# design.net
KiCad netlist of a schematic drawn in EAGLE
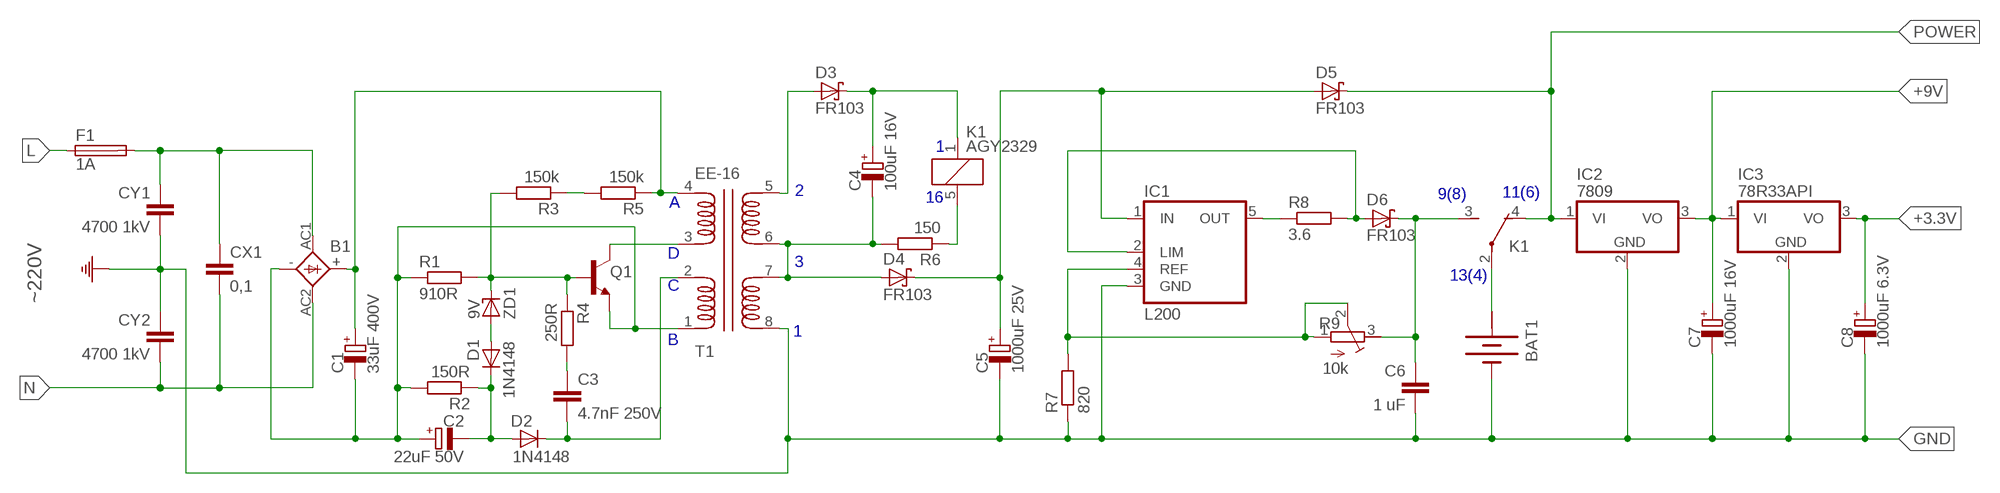
[diagram p0: schematic, sheet 1]

(export (version "E")
  (design (tool "Eeschema 10.0.6"))
  (components
    (comp (ref "B1")
      (value "1KAB")
      (footprint "eagle-import:1KAB")
      (libsource (lib "eagle-import") (part "1KAB"))
    )
    (comp (ref "BAT1")
      (value "BATTERY")
      (footprint "eagle-import:BATTERY")
      (libsource (lib "eagle-import") (part "BATTERY"))
    )
    (comp (ref "C1")
      (value "33uF 400V")
      (footprint "eagle-import:085CS_1AR")
      (libsource (lib "eagle-import") (part "CPOL-EU085CS-1AR"))
    )
    (comp (ref "C2")
      (value "22uF 50V")
      (footprint "eagle-import:085CS_1AR")
      (libsource (lib "eagle-import") (part "CPOL-EU085CS-1AR"))
    )
    (comp (ref "C3")
      (value "4.7nF 250V")
      (footprint "eagle-import:C025-024X044")
      (libsource (lib "eagle-import") (part "C-EU025-024X044"))
    )
    (comp (ref "C4")
      (value "100uF 16V")
      (footprint "eagle-import:085CS_1AR")
      (libsource (lib "eagle-import") (part "CPOL-EU085CS-1AR"))
    )
    (comp (ref "C5")
      (value "1000uF 25V")
      (footprint "eagle-import:085CS_1AR")
      (libsource (lib "eagle-import") (part "CPOL-EU085CS-1AR"))
    )
    (comp (ref "C6")
      (value "1 uF")
      (footprint "eagle-import:C025-024X044")
      (libsource (lib "eagle-import") (part "C-EU025-024X044"))
    )
    (comp (ref "C7")
      (value "1000uF 16V")
      (footprint "eagle-import:085CS_1AR")
      (libsource (lib "eagle-import") (part "CPOL-EU085CS-1AR"))
    )
    (comp (ref "C8")
      (value "1000uF 6.3V")
      (footprint "eagle-import:085CS_1AR")
      (libsource (lib "eagle-import") (part "CPOL-EU085CS-1AR"))
    )
    (comp (ref "CX1")
      (value "0,1")
      (footprint "eagle-import:C025-024X044")
      (libsource (lib "eagle-import") (part "C-EU025-024X044"))
    )
    (comp (ref "CY1")
      (value "4700 1kV")
      (footprint "eagle-import:C025-024X044")
      (libsource (lib "eagle-import") (part "C-EU025-024X044"))
    )
    (comp (ref "CY2")
      (value "4700 1kV")
      (footprint "eagle-import:C025-024X044")
      (libsource (lib "eagle-import") (part "C-EU025-024X044"))
    )
    (comp (ref "D1")
      (value "1N4148")
      (footprint "eagle-import:DO41-10")
      (libsource (lib "eagle-import") (part "1N4004"))
    )
    (comp (ref "D2")
      (value "1N4148")
      (footprint "eagle-import:DO41-10")
      (libsource (lib "eagle-import") (part "1N4004"))
    )
    (comp (ref "D3")
      (value "FR103")
      (footprint "eagle-import:SOT23")
      (libsource (lib "eagle-import") (part "BAS40"))
    )
    (comp (ref "D4")
      (value "FR103")
      (footprint "eagle-import:SOT23")
      (libsource (lib "eagle-import") (part "BAS40"))
    )
    (comp (ref "D5")
      (value "FR103")
      (footprint "eagle-import:SOT23")
      (libsource (lib "eagle-import") (part "BAS40"))
    )
    (comp (ref "D6")
      (value "FR103")
      (footprint "eagle-import:SOT23")
      (libsource (lib "eagle-import") (part "BAS40"))
    )
    (comp (ref "F1")
      (value "1А")
      (footprint "eagle-import:GSH15")
      (fields (field (name "MPN") "64900001039"))
      (libsource (lib "eagle-import") (part "GSH15"))
    )
    (comp (ref "IC1")
      (value "L200")
      (footprint "eagle-import:L200S")
      (libsource (lib "eagle-import") (part "L200"))
    )
    (comp (ref "IC2")
      (value "7809")
      (footprint "eagle-import:TO220H")
      (libsource (lib "eagle-import") (part "78T08"))
    )
    (comp (ref "IC3")
      (value "78R33API")
      (footprint "eagle-import:TO220H")
      (libsource (lib "eagle-import") (part "78T08"))
    )
    (comp (ref "K1")
      (value "AGY2329")
      (footprint "eagle-import:G5SB")
      (libsource (lib "eagle-import") (part "G5SB"))
    )
    (comp (ref "Q1")
      (value "2N706")
      (footprint "eagle-import:TO18")
      (libsource (lib "eagle-import") (part "2N706"))
    )
    (comp (ref "R1")
      (value "910R")
      (footprint "eagle-import:0204V")
      (libsource (lib "eagle-import") (part "R-EU_0204/2V"))
    )
    (comp (ref "R2")
      (value "150R")
      (footprint "eagle-import:0204V")
      (libsource (lib "eagle-import") (part "R-EU_0204/2V"))
    )
    (comp (ref "R3")
      (value "150k")
      (footprint "eagle-import:0204V")
      (libsource (lib "eagle-import") (part "R-EU_0204/2V"))
    )
    (comp (ref "R4")
      (value "250R")
      (footprint "eagle-import:0204V")
      (libsource (lib "eagle-import") (part "R-EU_0204/2V"))
    )
    (comp (ref "R5")
      (value "150k")
      (footprint "eagle-import:0204V")
      (libsource (lib "eagle-import") (part "R-EU_0204/2V"))
    )
    (comp (ref "R6")
      (value "150")
      (footprint "eagle-import:0204V")
      (libsource (lib "eagle-import") (part "R-EU_0204/2V"))
    )
    (comp (ref "R7")
      (value "820")
      (footprint "eagle-import:0204V")
      (libsource (lib "eagle-import") (part "R-EU_0204/2V"))
    )
    (comp (ref "R8")
      (value "3.6")
      (footprint "eagle-import:0204V")
      (libsource (lib "eagle-import") (part "R-EU_0204/2V"))
    )
    (comp (ref "R9")
      (value "10k")
      (footprint "eagle-import:RTRIM4G_J")
      (libsource (lib "eagle-import") (part "R-TRIMM4G/J"))
    )
    (comp (ref "T1")
      (value "EE-16")
      (footprint "eagle-import:HDS28G2")
      (libsource (lib "eagle-import") (part "HDS28G2"))
    )
    (comp (ref "ZD1")
      (value "9V")
      (footprint "eagle-import:C1702-15")
      (libsource (lib "eagle-import") (part "1N5333"))
    )
  )
  (nets
    (net (code "1") (name "+3.3V") (class "Default")
      (node (ref "C8") (pin "+") (pinfunction "+_+") (pintype "passive"))
      (node (ref "IC3") (pin "3") (pinfunction "VO_3") (pintype "passive"))
    )
    (net (code "2") (name "+9V") (class "Default")
      (node (ref "C7") (pin "+") (pinfunction "+_+") (pintype "passive"))
      (node (ref "IC2") (pin "3") (pinfunction "VO_3") (pintype "passive"))
      (node (ref "IC3") (pin "1") (pinfunction "VI_1") (pintype "input"))
    )
    (net (code "3") (name "/+") (class "Default")
      (node (ref "BAT1") (pin "+@1") (pinfunction "+_+@1") (pintype "power_in"))
    )
    (net (code "4") (name "GND") (class "Default")
      (node (ref "BAT1") (pin "-") (pinfunction "-_-") (pintype "power_in"))
      (node (ref "C5") (pin "-") (pinfunction "-_-") (pintype "passive"))
      (node (ref "C6") (pin "2") (pinfunction "2_2") (pintype "passive"))
      (node (ref "C7") (pin "-") (pinfunction "-_-") (pintype "passive"))
      (node (ref "C8") (pin "-") (pinfunction "-_-") (pintype "passive"))
      (node (ref "CY1") (pin "2") (pinfunction "2_2") (pintype "passive"))
      (node (ref "CY2") (pin "1") (pinfunction "1_1") (pintype "passive"))
      (node (ref "IC1") (pin "3") (pinfunction "GND_3") (pintype "passive"))
      (node (ref "IC2") (pin "2") (pinfunction "GND_2") (pintype "passive"))
      (node (ref "IC3") (pin "2") (pinfunction "GND_2") (pintype "passive"))
      (node (ref "R7") (pin "1") (pinfunction "1_1") (pintype "passive"))
      (node (ref "T1") (pin "8") (pinfunction "S1.1_8") (pintype "passive"))
    )
    (net (code "5") (name "L") (class "Default")
      (node (ref "F1") (pin "1") (pinfunction "1_1") (pintype "passive"))
    )
    (net (code "6") (name "N") (class "Default")
      (node (ref "B1") (pin "AC2") (pinfunction "AC2_AC2") (pintype "passive"))
      (node (ref "CX1") (pin "2") (pinfunction "2_2") (pintype "passive"))
      (node (ref "CY2") (pin "2") (pinfunction "2_2") (pintype "passive"))
    )
    (net (code "7") (name "Net-(B1-PadAC1)") (class "Default")
      (node (ref "B1") (pin "AC1") (pinfunction "AC1_AC1") (pintype "passive"))
      (node (ref "CX1") (pin "1") (pinfunction "1_1") (pintype "passive"))
      (node (ref "CY1") (pin "1") (pinfunction "1_1") (pintype "passive"))
      (node (ref "F1") (pin "2") (pinfunction "2_2") (pintype "passive"))
    )
    (net (code "8") (name "Net-(C2-Pad-)") (class "Default")
      (node (ref "C2") (pin "-") (pinfunction "-_-") (pintype "passive"))
      (node (ref "D1") (pin "C") (pinfunction "C_C") (pintype "passive"))
      (node (ref "D2") (pin "A") (pinfunction "A_A") (pintype "passive"))
      (node (ref "R2") (pin "1") (pinfunction "1_1") (pintype "passive"))
    )
    (net (code "9") (name "Net-(C3-Pad1)") (class "Default")
      (node (ref "C3") (pin "1") (pinfunction "1_1") (pintype "passive"))
      (node (ref "R4") (pin "2") (pinfunction "2_2") (pintype "passive"))
    )
    (net (code "10") (name "Net-(D1-PadA)") (class "Default")
      (node (ref "D1") (pin "A") (pinfunction "A_A") (pintype "passive"))
      (node (ref "ZD1") (pin "A") (pinfunction "A_A") (pintype "passive"))
    )
    (net (code "11") (name "Net-(D3-A)") (class "Default")
      (node (ref "D3") (pin "1") (pinfunction "A_1") (pintype "passive"))
      (node (ref "T1") (pin "5") (pinfunction "S2.2_5") (pintype "passive"))
    )
    (net (code "12") (name "Net-(D3-C)") (class "Default")
      (node (ref "C4") (pin "+") (pinfunction "+_+") (pintype "passive"))
      (node (ref "D3") (pin "3") (pinfunction "C_3") (pintype "passive"))
      (node (ref "K1") (pin "1") (pinfunction "1_1") (pintype "passive"))
    )
    (net (code "13") (name "Net-(D4-A)") (class "Default")
      (node (ref "C4") (pin "-") (pinfunction "-_-") (pintype "passive"))
      (node (ref "D4") (pin "1") (pinfunction "A_1") (pintype "passive"))
      (node (ref "R6") (pin "2") (pinfunction "2_2") (pintype "passive"))
      (node (ref "T1") (pin "6") (pinfunction "S2.1_6") (pintype "passive"))
      (node (ref "T1") (pin "7") (pinfunction "S1.2_7") (pintype "passive"))
    )
    (net (code "14") (name "Net-(D4-C)") (class "Default")
      (node (ref "C5") (pin "+") (pinfunction "+_+") (pintype "passive"))
      (node (ref "D4") (pin "3") (pinfunction "C_3") (pintype "passive"))
      (node (ref "D5") (pin "1") (pinfunction "A_1") (pintype "passive"))
      (node (ref "IC1") (pin "1") (pinfunction "IN_1") (pintype "input"))
    )
    (net (code "15") (name "Net-(D6-A)") (class "Default")
      (node (ref "D6") (pin "1") (pinfunction "A_1") (pintype "passive"))
      (node (ref "IC1") (pin "2") (pinfunction "LIM_2") (pintype "input"))
      (node (ref "R8") (pin "2") (pinfunction "2_2") (pintype "passive"))
    )
    (net (code "16") (name "Net-(D6-C)") (class "Default")
      (node (ref "C6") (pin "1") (pinfunction "1_1") (pintype "passive"))
      (node (ref "D6") (pin "3") (pinfunction "C_3") (pintype "passive"))
      (node (ref "K1") (pin "3") (pinfunction "S_3") (pintype "passive"))
      (node (ref "R9") (pin "3") (pinfunction "A_3") (pintype "passive"))
    )
    (net (code "17") (name "Net-(IC1-OUT)") (class "Default")
      (node (ref "IC1") (pin "5") (pinfunction "OUT_5") (pintype "passive"))
      (node (ref "R8") (pin "1") (pinfunction "1_1") (pintype "passive"))
    )
    (net (code "18") (name "Net-(IC1-REF)") (class "Default")
      (node (ref "IC1") (pin "4") (pinfunction "REF_4") (pintype "input"))
      (node (ref "R7") (pin "2") (pinfunction "2_2") (pintype "passive"))
      (node (ref "R9") (pin "1") (pinfunction "E_1") (pintype "passive"))
      (node (ref "R9") (pin "2") (pinfunction "S_2") (pintype "passive"))
    )
    (net (code "19") (name "Net-(K1A-2)") (class "Default")
      (node (ref "K1") (pin "5") (pinfunction "2_5") (pintype "passive"))
      (node (ref "R6") (pin "1") (pinfunction "1_1") (pintype "passive"))
    )
    (net (code "20") (name "Net-(K1B-P)") (class "Default")
      (node (ref "BAT1") (pin "+") (pinfunction "+_+") (pintype "power_in"))
      (node (ref "K1") (pin "2") (pinfunction "P_2") (pintype "passive"))
    )
    (net (code "21") (name "Net-(Q1-B)") (class "Default")
      (node (ref "Q1") (pin "2") (pinfunction "B_2") (pintype "passive"))
      (node (ref "R1") (pin "2") (pinfunction "2_2") (pintype "passive"))
      (node (ref "R3") (pin "2") (pinfunction "2_2") (pintype "passive"))
      (node (ref "R4") (pin "1") (pinfunction "1_1") (pintype "passive"))
      (node (ref "ZD1") (pin "C") (pinfunction "C_C") (pintype "passive"))
    )
    (net (code "22") (name "Net-(Q1-C)") (class "Default")
      (node (ref "Q1") (pin "3") (pinfunction "C_3") (pintype "passive"))
      (node (ref "T1") (pin "3") (pinfunction "P2.1_3") (pintype "passive"))
    )
    (net (code "23") (name "Net-(Q1-E)") (class "Default")
      (node (ref "B1") (pin "-") (pinfunction "-_-") (pintype "passive"))
      (node (ref "C1") (pin "-") (pinfunction "-_-") (pintype "passive"))
      (node (ref "C2") (pin "+") (pinfunction "+_+") (pintype "passive"))
      (node (ref "Q1") (pin "1") (pinfunction "E_1") (pintype "passive"))
      (node (ref "R1") (pin "1") (pinfunction "1_1") (pintype "passive"))
      (node (ref "R2") (pin "2") (pinfunction "2_2") (pintype "passive"))
      (node (ref "T1") (pin "1") (pinfunction "P1.1_1") (pintype "passive"))
    )
    (net (code "24") (name "Net-(R3-Pad1)") (class "Default")
      (node (ref "R3") (pin "1") (pinfunction "1_1") (pintype "passive"))
      (node (ref "R5") (pin "2") (pinfunction "2_2") (pintype "passive"))
    )
    (net (code "25") (name "Net-(T1-P1.2)") (class "Default")
      (node (ref "C3") (pin "2") (pinfunction "2_2") (pintype "passive"))
      (node (ref "D2") (pin "C") (pinfunction "C_C") (pintype "passive"))
      (node (ref "T1") (pin "2") (pinfunction "P1.2_2") (pintype "passive"))
    )
    (net (code "26") (name "Net-(T1-P2.2)") (class "Default")
      (node (ref "B1") (pin "+") (pinfunction "+_+") (pintype "passive"))
      (node (ref "C1") (pin "+") (pinfunction "+_+") (pintype "passive"))
      (node (ref "R5") (pin "1") (pinfunction "1_1") (pintype "passive"))
      (node (ref "T1") (pin "4") (pinfunction "P2.2_4") (pintype "passive"))
    )
    (net (code "27") (name "POWER") (class "Default")
      (node (ref "D5") (pin "3") (pinfunction "C_3") (pintype "passive"))
      (node (ref "IC2") (pin "1") (pinfunction "VI_1") (pintype "input"))
      (node (ref "K1") (pin "4") (pinfunction "O_4") (pintype "passive"))
    )
  )
)
